# FiltroPB_acoplado.net
KiCad netlist of a schematic drawn in Altium Designer
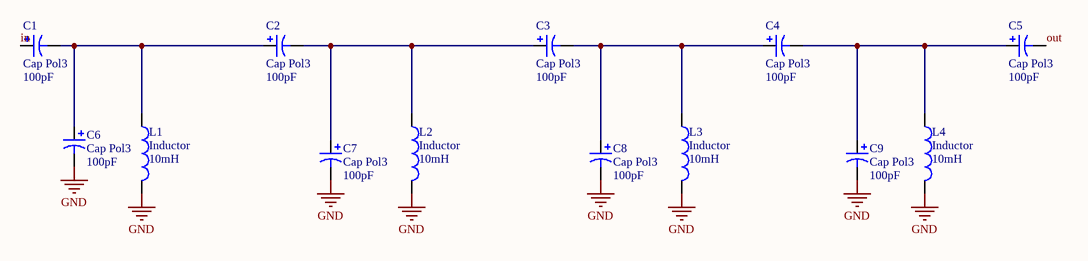
[diagram p0: FiltroPB_acoplado.SchDoc]

(export (version "E")
  (design (tool "Eeschema 10.0.6"))
  (components
    (comp (ref "C1")
      (value "Cap Pol3")
      (footprint "C0805")
      (description "Polarized Capacitor (Surface Mount)")
      (fields (field (name "ALTIUM_VALUE") "100pF") (field (name "PUBLISHER") "Altium Limited"))
      (libsource (lib "Miscellaneous Devices") (part "Cap Pol3"))
    )
    (comp (ref "C2")
      (value "Cap Pol3")
      (footprint "C0805")
      (description "Polarized Capacitor (Surface Mount)")
      (fields (field (name "ALTIUM_VALUE") "100pF") (field (name "PUBLISHER") "Altium Limited"))
      (libsource (lib "Miscellaneous Devices") (part "Cap Pol3"))
    )
    (comp (ref "C3")
      (value "Cap Pol3")
      (footprint "C0805")
      (description "Polarized Capacitor (Surface Mount)")
      (fields (field (name "ALTIUM_VALUE") "100pF") (field (name "PUBLISHER") "Altium Limited"))
      (libsource (lib "Miscellaneous Devices") (part "Cap Pol3"))
    )
    (comp (ref "C4")
      (value "Cap Pol3")
      (footprint "C0805")
      (description "Polarized Capacitor (Surface Mount)")
      (fields (field (name "ALTIUM_VALUE") "100pF") (field (name "PUBLISHER") "Altium Limited"))
      (libsource (lib "Miscellaneous Devices") (part "Cap Pol3"))
    )
    (comp (ref "C5")
      (value "Cap Pol3")
      (footprint "C0805")
      (description "Polarized Capacitor (Surface Mount)")
      (fields (field (name "ALTIUM_VALUE") "100pF") (field (name "PUBLISHER") "Altium Limited"))
      (libsource (lib "Miscellaneous Devices") (part "Cap Pol3"))
    )
    (comp (ref "C6")
      (value "Cap Pol3")
      (footprint "C0805")
      (description "Polarized Capacitor (Surface Mount)")
      (fields (field (name "ALTIUM_VALUE") "100pF") (field (name "PUBLISHER") "Altium Limited"))
      (libsource (lib "Miscellaneous Devices") (part "Cap Pol3"))
    )
    (comp (ref "C7")
      (value "Cap Pol3")
      (footprint "C0805")
      (description "Polarized Capacitor (Surface Mount)")
      (fields (field (name "ALTIUM_VALUE") "100pF") (field (name "PUBLISHER") "Altium Limited"))
      (libsource (lib "Miscellaneous Devices") (part "Cap Pol3"))
    )
    (comp (ref "C8")
      (value "Cap Pol3")
      (footprint "C0805")
      (description "Polarized Capacitor (Surface Mount)")
      (fields (field (name "ALTIUM_VALUE") "100pF") (field (name "PUBLISHER") "Altium Limited"))
      (libsource (lib "Miscellaneous Devices") (part "Cap Pol3"))
    )
    (comp (ref "C9")
      (value "Cap Pol3")
      (footprint "C0805")
      (description "Polarized Capacitor (Surface Mount)")
      (fields (field (name "ALTIUM_VALUE") "100pF") (field (name "PUBLISHER") "Altium Limited"))
      (libsource (lib "Miscellaneous Devices") (part "Cap Pol3"))
    )
    (comp (ref "L1")
      (value "Inductor")
      (footprint "0402-A")
      (fields (field (name "ALTIUM_VALUE") "10mH") (field (name "PUBLISHER") "Altium Limited"))
      (libsource (lib "Miscellaneous Devices") (part "Inductor"))
    )
    (comp (ref "L2")
      (value "Inductor")
      (footprint "0402-A")
      (fields (field (name "ALTIUM_VALUE") "10mH") (field (name "PUBLISHER") "Altium Limited"))
      (libsource (lib "Miscellaneous Devices") (part "Inductor"))
    )
    (comp (ref "L3")
      (value "Inductor")
      (footprint "0402-A")
      (fields (field (name "ALTIUM_VALUE") "10mH") (field (name "PUBLISHER") "Altium Limited"))
      (libsource (lib "Miscellaneous Devices") (part "Inductor"))
    )
    (comp (ref "L4")
      (value "Inductor")
      (footprint "0402-A")
      (fields (field (name "ALTIUM_VALUE") "10mH") (field (name "PUBLISHER") "Altium Limited"))
      (libsource (lib "Miscellaneous Devices") (part "Inductor"))
    )
  )
  (nets
    (net (code "1") (name "/in") (class "Default")
      (node (ref "C1") (pin "1") (pinfunction "1_1") (pintype "passive"))
    )
    (net (code "2") (name "/out") (class "Default")
      (node (ref "C5") (pin "2") (pinfunction "2_2") (pintype "passive"))
    )
    (net (code "3") (name "GND") (class "Default")
      (node (ref "C6") (pin "2") (pinfunction "2_2") (pintype "passive"))
      (node (ref "C7") (pin "2") (pinfunction "2_2") (pintype "passive"))
      (node (ref "C8") (pin "2") (pinfunction "2_2") (pintype "passive"))
      (node (ref "C9") (pin "2") (pinfunction "2_2") (pintype "passive"))
      (node (ref "L1") (pin "2") (pinfunction "2_2") (pintype "passive"))
      (node (ref "L2") (pin "2") (pinfunction "2_2") (pintype "passive"))
      (node (ref "L3") (pin "2") (pinfunction "2_2") (pintype "passive"))
      (node (ref "L4") (pin "2") (pinfunction "2_2") (pintype "passive"))
    )
    (net (code "4") (name "Net-(C1-Pad2)") (class "Default")
      (node (ref "C1") (pin "2") (pinfunction "2_2") (pintype "passive"))
      (node (ref "C2") (pin "1") (pinfunction "1_1") (pintype "passive"))
      (node (ref "C6") (pin "1") (pinfunction "1_1") (pintype "passive"))
      (node (ref "L1") (pin "1") (pinfunction "1_1") (pintype "passive"))
    )
    (net (code "5") (name "Net-(C2-Pad2)") (class "Default")
      (node (ref "C2") (pin "2") (pinfunction "2_2") (pintype "passive"))
      (node (ref "C3") (pin "1") (pinfunction "1_1") (pintype "passive"))
      (node (ref "C7") (pin "1") (pinfunction "1_1") (pintype "passive"))
      (node (ref "L2") (pin "1") (pinfunction "1_1") (pintype "passive"))
    )
    (net (code "6") (name "Net-(C3-Pad2)") (class "Default")
      (node (ref "C3") (pin "2") (pinfunction "2_2") (pintype "passive"))
      (node (ref "C4") (pin "1") (pinfunction "1_1") (pintype "passive"))
      (node (ref "C8") (pin "1") (pinfunction "1_1") (pintype "passive"))
      (node (ref "L3") (pin "1") (pinfunction "1_1") (pintype "passive"))
    )
    (net (code "7") (name "Net-(C4-Pad2)") (class "Default")
      (node (ref "C4") (pin "2") (pinfunction "2_2") (pintype "passive"))
      (node (ref "C5") (pin "1") (pinfunction "1_1") (pintype "passive"))
      (node (ref "C9") (pin "1") (pinfunction "1_1") (pintype "passive"))
      (node (ref "L4") (pin "1") (pinfunction "1_1") (pintype "passive"))
    )
  )
)
